# main_board.net
KiCad netlist of a schematic drawn in Altium Designer
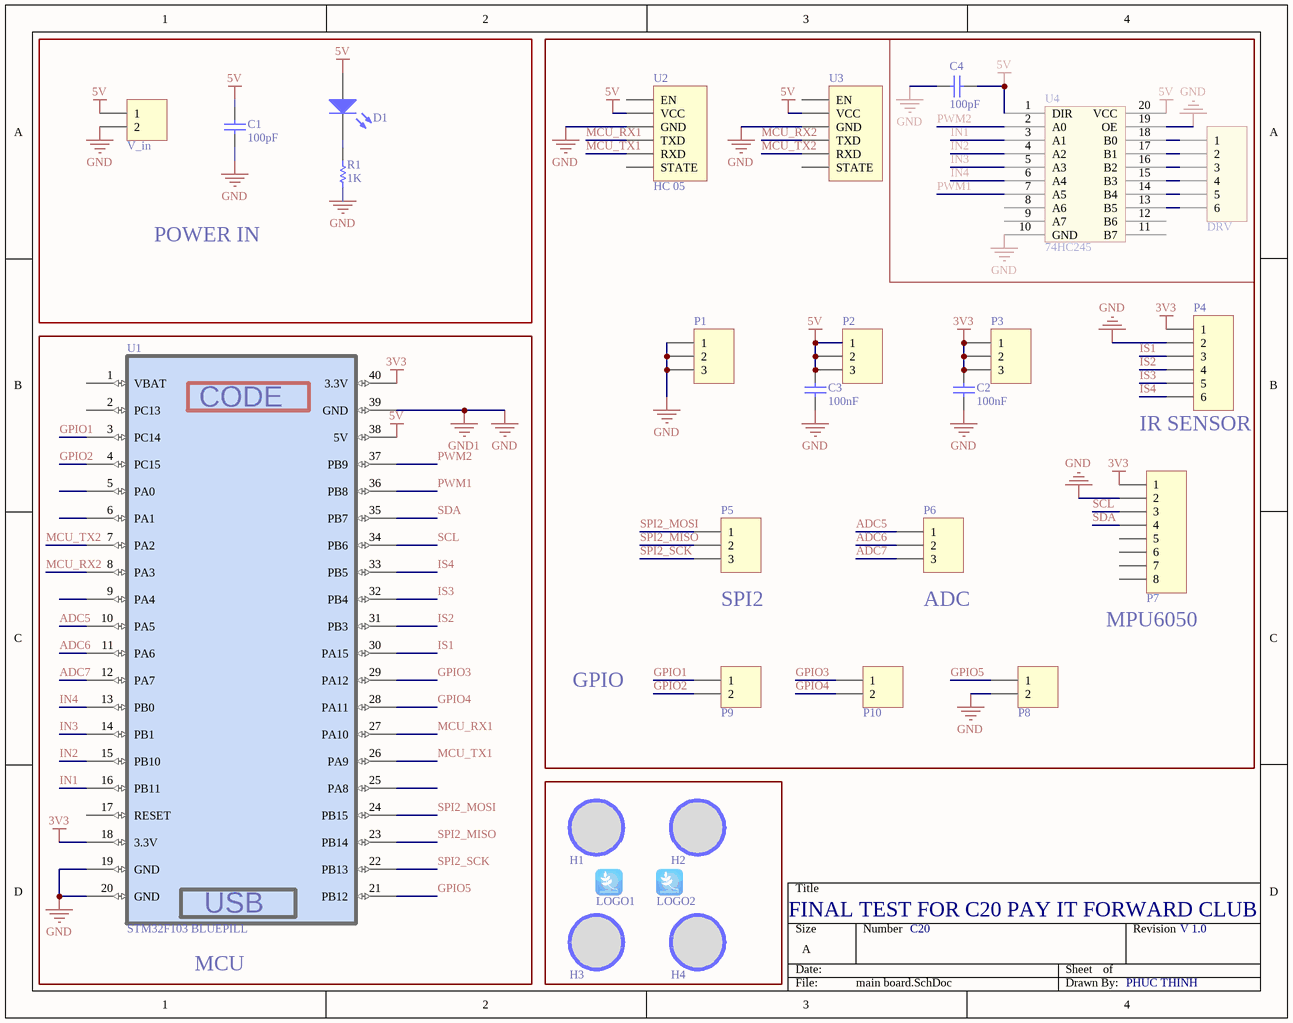
[diagram p0: main board.SchDoc]

(export (version "E")
  (design (tool "Eeschema 10.0.6"))
  (components
    (comp (ref "C1")
      (value "100pF")
      (footprint "CAP-SM-0805")
      (description "Capacitor")
      (fields (field (name "Comment") "Cap Non-Pol SMD"))
      (libsource (lib "PIF_Schematic_Lib") (part "Cap Non-Pol SMD"))
    )
    (comp (ref "C2")
      (value "100nF")
      (footprint "CAP-SM-0805")
      (description "Capacitor")
      (fields (field (name "Comment") "Cap Non-Pol SMD"))
      (libsource (lib "PIF_Schematic_Lib") (part "Cap Non-Pol SMD"))
    )
    (comp (ref "C3")
      (value "100nF")
      (footprint "CAP-SM-0805")
      (description "Capacitor")
      (fields (field (name "Comment") "Cap Non-Pol SMD"))
      (libsource (lib "PIF_Schematic_Lib") (part "Cap Non-Pol SMD"))
    )
    (comp (ref "C4")
      (value "100pF")
      (footprint "CAP-SM-0805")
      (description "Capacitor")
      (fields (field (name "Comment") "Cap Non-Pol SMD"))
      (libsource (lib "PIF_Schematic_Lib") (part "Cap Non-Pol SMD"))
    )
    (comp (ref "D1") (value "LED") (footprint "LED-3mm") (libsource (lib "PIF_Schematic_Lib") (part "LED")))
    (comp (ref "DRV")
      (value "Header 6")
      (footprint "JP6")
      (description "Header, 6-Pin")
      (fields (field (name "PUBLISHER") "Altium Limited"))
      (libsource (lib "PIF_Schematic_Lib") (part "Header 6"))
    )
    (comp (ref "H1")
      (value "Hole")
      (footprint "LO KHOAN 3MM")
      (description "Hole 3mm")
      (libsource (lib "PIF_Schematic_Lib") (part "Hole"))
    )
    (comp (ref "H2")
      (value "Hole")
      (footprint "LO KHOAN 3MM")
      (description "Hole 3mm")
      (libsource (lib "PIF_Schematic_Lib") (part "Hole"))
    )
    (comp (ref "H3")
      (value "Hole")
      (footprint "LO KHOAN 3MM")
      (description "Hole 3mm")
      (libsource (lib "PIF_Schematic_Lib") (part "Hole"))
    )
    (comp (ref "H4")
      (value "Hole")
      (footprint "LO KHOAN 3MM")
      (description "Hole 3mm")
      (libsource (lib "PIF_Schematic_Lib") (part "Hole"))
    )
    (comp (ref "LOGO1")
      (value "LOGO PIF")
      (footprint "PIF LOGO TOP OVERLAY")
      (libsource (lib "PIF_Schematic_Lib") (part "LOGO PIF_2"))
    )
    (comp (ref "LOGO2")
      (value "LOGO PIF")
      (footprint "PIF LOGO TOP OVERLAY")
      (libsource (lib "PIF_Schematic_Lib") (part "LOGO PIF_2"))
    )
    (comp (ref "P1")
      (value "Header 3")
      (footprint "JP3")
      (description "Header, 3-Pin")
      (fields (field (name "PUBLISHER") "Altium Limited"))
      (libsource (lib "PIF_Schematic_Lib") (part "Header 3"))
    )
    (comp (ref "P2")
      (value "Header 3")
      (footprint "JP3")
      (description "Header, 3-Pin")
      (fields (field (name "PUBLISHER") "Altium Limited"))
      (libsource (lib "PIF_Schematic_Lib") (part "Header 3"))
    )
    (comp (ref "P3")
      (value "Header 3")
      (footprint "JP3")
      (description "Header, 3-Pin")
      (fields (field (name "PUBLISHER") "Altium Limited"))
      (libsource (lib "PIF_Schematic_Lib") (part "Header 3"))
    )
    (comp (ref "P4")
      (value "Header 6")
      (footprint "JP6")
      (description "Header, 6-Pin")
      (fields (field (name "PUBLISHER") "Altium Limited"))
      (libsource (lib "PIF_Schematic_Lib") (part "Header 6"))
    )
    (comp (ref "P5")
      (value "Header 3")
      (footprint "JP3")
      (description "Header, 3-Pin")
      (fields (field (name "PUBLISHER") "Altium Limited"))
      (libsource (lib "PIF_Schematic_Lib") (part "Header 3"))
    )
    (comp (ref "P6")
      (value "Header 3")
      (footprint "JP3")
      (description "Header, 3-Pin")
      (fields (field (name "PUBLISHER") "Altium Limited"))
      (libsource (lib "PIF_Schematic_Lib") (part "Header 3"))
    )
    (comp (ref "P7")
      (value "Header 8")
      (footprint "JP8")
      (description "Header, 8-Pin")
      (fields (field (name "PUBLISHER") "Altium Limited"))
      (libsource (lib "PIF_Schematic_Lib") (part "Header 8"))
    )
    (comp (ref "P8")
      (value "Header 2")
      (footprint "JP2")
      (description "Header, 2-Pin")
      (fields (field (name "PUBLISHER") "Altium Limited"))
      (libsource (lib "PIF_Schematic_Lib") (part "Header 2"))
    )
    (comp (ref "P9")
      (value "Header 2")
      (footprint "JP2")
      (description "Header, 2-Pin")
      (fields (field (name "PUBLISHER") "Altium Limited"))
      (libsource (lib "PIF_Schematic_Lib") (part "Header 2"))
    )
    (comp (ref "P10")
      (value "Header 2")
      (footprint "JP2")
      (description "Header, 2-Pin")
      (fields (field (name "PUBLISHER") "Altium Limited"))
      (libsource (lib "PIF_Schematic_Lib") (part "Header 2"))
    )
    (comp (ref "R1")
      (value "1K")
      (footprint "RES-SM-0603")
      (description "Resistor")
      (fields (field (name "Comment") "RESISTOR SMD"))
      (libsource (lib "PIF_Schematic_Lib") (part "RESISTOR SMD"))
    )
    (comp (ref "U1")
      (value "STM32F103 BLUEPILL")
      (footprint "STM32F103 Bluepill")
      (libsource (lib "PIF_Schematic_Lib") (part "STM32F103 BLUEPILL"))
    )
    (comp (ref "U2") (value "HC 05") (footprint "JP6") (libsource (lib "PIF_Schematic_Lib") (part "HC 05")))
    (comp (ref "U3") (value "HC 05") (footprint "JP6") (libsource (lib "PIF_Schematic_Lib") (part "HC 05")))
    (comp (ref "U4")
      (value "74HC245")
      (footprint "DIP20/W0.3")
      (description "Octal bus tranceiver")
      (libsource (lib "PIF_Schematic_Lib") (part "74HC245"))
    )
    (comp (ref "V_in")
      (value "Domino 2")
      (footprint "DOMINO 2- 5mm")
      (description "Domino, 2-Pin")
      (fields (field (name "PUBLISHER") "Altium Limited"))
      (libsource (lib "PIF_Schematic_Lib") (part "Domino 2"))
    )
  )
  (nets
    (net (code "1") (name "/ADC5") (class "Default")
      (node (ref "P6") (pin "1") (pinfunction "1_1") (pintype "passive"))
      (node (ref "U1") (pin "10") (pinfunction "PA5_10") (pintype "bidirectional"))
    )
    (net (code "2") (name "/ADC6") (class "Default")
      (node (ref "P6") (pin "2") (pinfunction "2_2") (pintype "passive"))
      (node (ref "U1") (pin "11") (pinfunction "PA6_11") (pintype "bidirectional"))
    )
    (net (code "3") (name "/ADC7") (class "Default")
      (node (ref "P6") (pin "3") (pinfunction "3_3") (pintype "passive"))
      (node (ref "U1") (pin "12") (pinfunction "PA7_12") (pintype "bidirectional"))
    )
    (net (code "4") (name "/GPIO1") (class "Default")
      (node (ref "P9") (pin "1") (pinfunction "1_1") (pintype "passive"))
      (node (ref "U1") (pin "3") (pinfunction "PC14_3") (pintype "bidirectional"))
    )
    (net (code "5") (name "/GPIO2") (class "Default")
      (node (ref "P9") (pin "2") (pinfunction "2_2") (pintype "passive"))
      (node (ref "U1") (pin "4") (pinfunction "PC15_4") (pintype "bidirectional"))
    )
    (net (code "6") (name "/GPIO3") (class "Default")
      (node (ref "P10") (pin "1") (pinfunction "1_1") (pintype "passive"))
      (node (ref "U1") (pin "29") (pinfunction "PA12_29") (pintype "bidirectional"))
    )
    (net (code "7") (name "/GPIO4") (class "Default")
      (node (ref "P10") (pin "2") (pinfunction "2_2") (pintype "passive"))
      (node (ref "U1") (pin "28") (pinfunction "PA11_28") (pintype "bidirectional"))
    )
    (net (code "8") (name "/GPIO5") (class "Default")
      (node (ref "P8") (pin "1") (pinfunction "1_1") (pintype "passive"))
      (node (ref "U1") (pin "21") (pinfunction "PB12_21") (pintype "bidirectional"))
    )
    (net (code "9") (name "/IN1") (class "Default")
      (node (ref "U1") (pin "16") (pinfunction "PB11_16") (pintype "bidirectional"))
      (node (ref "U4") (pin "3") (pinfunction "A1_3") (pintype "passive"))
    )
    (net (code "10") (name "/IN2") (class "Default")
      (node (ref "U1") (pin "15") (pinfunction "PB10_15") (pintype "bidirectional"))
      (node (ref "U4") (pin "4") (pinfunction "A2_4") (pintype "passive"))
    )
    (net (code "11") (name "/IN3") (class "Default")
      (node (ref "U1") (pin "14") (pinfunction "PB1_14") (pintype "bidirectional"))
      (node (ref "U4") (pin "5") (pinfunction "A3_5") (pintype "passive"))
    )
    (net (code "12") (name "/IN4") (class "Default")
      (node (ref "U1") (pin "13") (pinfunction "PB0_13") (pintype "bidirectional"))
      (node (ref "U4") (pin "6") (pinfunction "A4_6") (pintype "passive"))
    )
    (net (code "13") (name "/IS1") (class "Default")
      (node (ref "P4") (pin "3") (pinfunction "3_3") (pintype "passive"))
      (node (ref "U1") (pin "30") (pinfunction "PA15_30") (pintype "bidirectional"))
    )
    (net (code "14") (name "/IS2") (class "Default")
      (node (ref "P4") (pin "4") (pinfunction "4_4") (pintype "passive"))
      (node (ref "U1") (pin "31") (pinfunction "PB3_31") (pintype "bidirectional"))
    )
    (net (code "15") (name "/IS3") (class "Default")
      (node (ref "P4") (pin "5") (pinfunction "5_5") (pintype "passive"))
      (node (ref "U1") (pin "32") (pinfunction "PB4_32") (pintype "bidirectional"))
    )
    (net (code "16") (name "/IS4") (class "Default")
      (node (ref "P4") (pin "6") (pinfunction "6_6") (pintype "passive"))
      (node (ref "U1") (pin "33") (pinfunction "PB5_33") (pintype "bidirectional"))
    )
    (net (code "17") (name "/MCU_RX1") (class "Default")
      (node (ref "U1") (pin "27") (pinfunction "PA10_27") (pintype "bidirectional"))
      (node (ref "U2") (pin "4") (pinfunction "TXD_4") (pintype "passive"))
    )
    (net (code "18") (name "/MCU_RX2") (class "Default")
      (node (ref "U1") (pin "8") (pinfunction "PA3_8") (pintype "bidirectional"))
      (node (ref "U3") (pin "4") (pinfunction "TXD_4") (pintype "passive"))
    )
    (net (code "19") (name "/MCU_TX1") (class "Default")
      (node (ref "U1") (pin "26") (pinfunction "PA9_26") (pintype "bidirectional"))
      (node (ref "U2") (pin "5") (pinfunction "RXD_5") (pintype "passive"))
    )
    (net (code "20") (name "/MCU_TX2") (class "Default")
      (node (ref "U1") (pin "7") (pinfunction "PA2_7") (pintype "bidirectional"))
      (node (ref "U3") (pin "5") (pinfunction "RXD_5") (pintype "passive"))
    )
    (net (code "21") (name "/PWM1") (class "Default")
      (node (ref "U1") (pin "36") (pinfunction "PB8_36") (pintype "bidirectional"))
      (node (ref "U4") (pin "7") (pinfunction "A5_7") (pintype "passive"))
    )
    (net (code "22") (name "/PWM2") (class "Default")
      (node (ref "U1") (pin "37") (pinfunction "PB9_37") (pintype "bidirectional"))
      (node (ref "U4") (pin "2") (pinfunction "A0_2") (pintype "passive"))
    )
    (net (code "23") (name "/SCL") (class "Default")
      (node (ref "P7") (pin "3") (pinfunction "3_3") (pintype "passive"))
      (node (ref "U1") (pin "34") (pinfunction "PB6_34") (pintype "bidirectional"))
    )
    (net (code "24") (name "/SDA") (class "Default")
      (node (ref "P7") (pin "4") (pinfunction "4_4") (pintype "passive"))
      (node (ref "U1") (pin "35") (pinfunction "PB7_35") (pintype "bidirectional"))
    )
    (net (code "25") (name "/SPI2_MISO") (class "Default")
      (node (ref "P5") (pin "2") (pinfunction "2_2") (pintype "passive"))
      (node (ref "U1") (pin "23") (pinfunction "PB14_23") (pintype "bidirectional"))
    )
    (net (code "26") (name "/SPI2_MOSI") (class "Default")
      (node (ref "P5") (pin "1") (pinfunction "1_1") (pintype "passive"))
      (node (ref "U1") (pin "24") (pinfunction "PB15_24") (pintype "bidirectional"))
    )
    (net (code "27") (name "/SPI2_SCK") (class "Default")
      (node (ref "P5") (pin "3") (pinfunction "3_3") (pintype "passive"))
      (node (ref "U1") (pin "22") (pinfunction "PB13_22") (pintype "bidirectional"))
    )
    (net (code "28") (name "3V3") (class "Default")
      (node (ref "C2") (pin "2") (pinfunction "2_2") (pintype "passive"))
      (node (ref "P3") (pin "1") (pinfunction "1_1") (pintype "passive"))
      (node (ref "P3") (pin "2") (pinfunction "2_2") (pintype "passive"))
      (node (ref "P3") (pin "3") (pinfunction "3_3") (pintype "passive"))
      (node (ref "P4") (pin "1") (pinfunction "1_1") (pintype "passive"))
      (node (ref "P7") (pin "1") (pinfunction "1_1") (pintype "passive"))
      (node (ref "U1") (pin "18") (pinfunction "3.3V_18") (pintype "bidirectional"))
      (node (ref "U1") (pin "40") (pinfunction "3.3V_40") (pintype "bidirectional"))
    )
    (net (code "29") (name "5V") (class "Default")
      (node (ref "C1") (pin "2") (pinfunction "2_2") (pintype "passive"))
      (node (ref "C3") (pin "2") (pinfunction "2_2") (pintype "passive"))
      (node (ref "C4") (pin "2") (pinfunction "2_2") (pintype "passive"))
      (node (ref "D1") (pin "1") (pinfunction "A_1") (pintype "passive"))
      (node (ref "P2") (pin "1") (pinfunction "1_1") (pintype "passive"))
      (node (ref "P2") (pin "2") (pinfunction "2_2") (pintype "passive"))
      (node (ref "P2") (pin "3") (pinfunction "3_3") (pintype "passive"))
      (node (ref "U1") (pin "38") (pinfunction "5V_38") (pintype "bidirectional"))
      (node (ref "U2") (pin "2") (pinfunction "VCC_2") (pintype "passive"))
      (node (ref "U3") (pin "2") (pinfunction "VCC_2") (pintype "passive"))
      (node (ref "U4") (pin "1") (pinfunction "DIR_1") (pintype "passive"))
      (node (ref "U4") (pin "20") (pinfunction "VCC_20") (pintype "power_in"))
      (node (ref "V_in") (pin "1") (pinfunction "1_1") (pintype "passive"))
    )
    (net (code "30") (name "GND") (class "Default")
      (node (ref "C1") (pin "1") (pinfunction "1_1") (pintype "passive"))
      (node (ref "C2") (pin "1") (pinfunction "1_1") (pintype "passive"))
      (node (ref "C3") (pin "1") (pinfunction "1_1") (pintype "passive"))
      (node (ref "C4") (pin "1") (pinfunction "1_1") (pintype "passive"))
      (node (ref "P1") (pin "1") (pinfunction "1_1") (pintype "passive"))
      (node (ref "P1") (pin "2") (pinfunction "2_2") (pintype "passive"))
      (node (ref "P1") (pin "3") (pinfunction "3_3") (pintype "passive"))
      (node (ref "P4") (pin "2") (pinfunction "2_2") (pintype "passive"))
      (node (ref "P7") (pin "2") (pinfunction "2_2") (pintype "passive"))
      (node (ref "P8") (pin "2") (pinfunction "2_2") (pintype "passive"))
      (node (ref "R1") (pin "1") (pinfunction "1_1") (pintype "passive"))
      (node (ref "U1") (pin "19") (pinfunction "GND_19") (pintype "bidirectional"))
      (node (ref "U1") (pin "20") (pinfunction "GND_20") (pintype "bidirectional"))
      (node (ref "U1") (pin "39") (pinfunction "GND_39") (pintype "bidirectional"))
      (node (ref "U2") (pin "3") (pinfunction "GND_3") (pintype "passive"))
      (node (ref "U3") (pin "3") (pinfunction "GND_3") (pintype "passive"))
      (node (ref "U4") (pin "10") (pinfunction "GND_10") (pintype "power_in"))
      (node (ref "U4") (pin "19") (pinfunction "OE_19") (pintype "passive"))
      (node (ref "V_in") (pin "2") (pinfunction "2_2") (pintype "passive"))
    )
    (net (code "31") (name "Net-(D1-K)") (class "Default")
      (node (ref "D1") (pin "2") (pinfunction "K_2") (pintype "passive"))
      (node (ref "R1") (pin "2") (pinfunction "2_2") (pintype "passive"))
    )
    (net (code "32") (name "Net-(U4-B0)") (class "Default")
      (node (ref "DRV") (pin "1") (pinfunction "1_1") (pintype "passive"))
      (node (ref "U4") (pin "18") (pinfunction "B0_18") (pintype "passive"))
    )
    (net (code "33") (name "Net-(U4-B1)") (class "Default")
      (node (ref "DRV") (pin "2") (pinfunction "2_2") (pintype "passive"))
      (node (ref "U4") (pin "17") (pinfunction "B1_17") (pintype "passive"))
    )
    (net (code "34") (name "Net-(U4-B2)") (class "Default")
      (node (ref "DRV") (pin "3") (pinfunction "3_3") (pintype "passive"))
      (node (ref "U4") (pin "16") (pinfunction "B2_16") (pintype "passive"))
    )
    (net (code "35") (name "Net-(U4-B3)") (class "Default")
      (node (ref "DRV") (pin "4") (pinfunction "4_4") (pintype "passive"))
      (node (ref "U4") (pin "15") (pinfunction "B3_15") (pintype "passive"))
    )
    (net (code "36") (name "Net-(U4-B4)") (class "Default")
      (node (ref "DRV") (pin "5") (pinfunction "5_5") (pintype "passive"))
      (node (ref "U4") (pin "14") (pinfunction "B4_14") (pintype "passive"))
    )
    (net (code "37") (name "Net-(U4-B5)") (class "Default")
      (node (ref "DRV") (pin "6") (pinfunction "6_6") (pintype "passive"))
      (node (ref "U4") (pin "13") (pinfunction "B5_13") (pintype "passive"))
    )
    (net (code "38") (name "unconnected-(H1-Pad1)") (class "Default")
      (node (ref "H1") (pin "1") (pinfunction "1_1") (pintype "passive"))
    )
    (net (code "39") (name "unconnected-(H2-Pad1)") (class "Default")
      (node (ref "H2") (pin "1") (pinfunction "1_1") (pintype "passive"))
    )
    (net (code "40") (name "unconnected-(H3-Pad1)") (class "Default")
      (node (ref "H3") (pin "1") (pinfunction "1_1") (pintype "passive"))
    )
    (net (code "41") (name "unconnected-(H4-Pad1)") (class "Default")
      (node (ref "H4") (pin "1") (pinfunction "1_1") (pintype "passive"))
    )
    (net (code "42") (name "unconnected-(P7-Pad5)") (class "Default")
      (node (ref "P7") (pin "5") (pinfunction "5_5") (pintype "passive"))
    )
    (net (code "43") (name "unconnected-(P7-Pad6)") (class "Default")
      (node (ref "P7") (pin "6") (pinfunction "6_6") (pintype "passive"))
    )
    (net (code "44") (name "unconnected-(P7-Pad7)") (class "Default")
      (node (ref "P7") (pin "7") (pinfunction "7_7") (pintype "passive"))
    )
    (net (code "45") (name "unconnected-(P7-Pad8)") (class "Default")
      (node (ref "P7") (pin "8") (pinfunction "8_8") (pintype "passive"))
    )
    (net (code "46") (name "unconnected-(U1-PA0-Pad5)") (class "Default")
      (node (ref "U1") (pin "5") (pinfunction "PA0_5") (pintype "bidirectional"))
    )
    (net (code "47") (name "unconnected-(U1-PA1-Pad6)") (class "Default")
      (node (ref "U1") (pin "6") (pinfunction "PA1_6") (pintype "bidirectional"))
    )
    (net (code "48") (name "unconnected-(U1-PA4-Pad9)") (class "Default")
      (node (ref "U1") (pin "9") (pinfunction "PA4_9") (pintype "bidirectional"))
    )
    (net (code "49") (name "unconnected-(U1-PA8-Pad25)") (class "Default")
      (node (ref "U1") (pin "25") (pinfunction "PA8_25") (pintype "bidirectional"))
    )
    (net (code "50") (name "unconnected-(U1-PC13-Pad2)") (class "Default")
      (node (ref "U1") (pin "2") (pinfunction "PC13_2") (pintype "bidirectional"))
    )
    (net (code "51") (name "unconnected-(U1-RESET-Pad17)") (class "Default")
      (node (ref "U1") (pin "17") (pinfunction "RESET_17") (pintype "bidirectional"))
    )
    (net (code "52") (name "unconnected-(U1-VBAT-Pad1)") (class "Default")
      (node (ref "U1") (pin "1") (pinfunction "VBAT_1") (pintype "bidirectional"))
    )
    (net (code "53") (name "unconnected-(U2-EN-Pad1)") (class "Default")
      (node (ref "U2") (pin "1") (pinfunction "EN_1") (pintype "passive"))
    )
    (net (code "54") (name "unconnected-(U2-STATE-Pad6)") (class "Default")
      (node (ref "U2") (pin "6") (pinfunction "STATE_6") (pintype "passive"))
    )
    (net (code "55") (name "unconnected-(U3-EN-Pad1)") (class "Default")
      (node (ref "U3") (pin "1") (pinfunction "EN_1") (pintype "passive"))
    )
    (net (code "56") (name "unconnected-(U3-STATE-Pad6)") (class "Default")
      (node (ref "U3") (pin "6") (pinfunction "STATE_6") (pintype "passive"))
    )
    (net (code "57") (name "unconnected-(U4-A6-Pad8)") (class "Default")
      (node (ref "U4") (pin "8") (pinfunction "A6_8") (pintype "passive"))
    )
    (net (code "58") (name "unconnected-(U4-A7-Pad9)") (class "Default")
      (node (ref "U4") (pin "9") (pinfunction "A7_9") (pintype "passive"))
    )
    (net (code "59") (name "unconnected-(U4-B6-Pad12)") (class "Default")
      (node (ref "U4") (pin "12") (pinfunction "B6_12") (pintype "passive"))
    )
    (net (code "60") (name "unconnected-(U4-B7-Pad11)") (class "Default")
      (node (ref "U4") (pin "11") (pinfunction "B7_11") (pintype "passive"))
    )
  )
)
